# Drive.net
KiCad netlist of a schematic drawn in Altium Designer
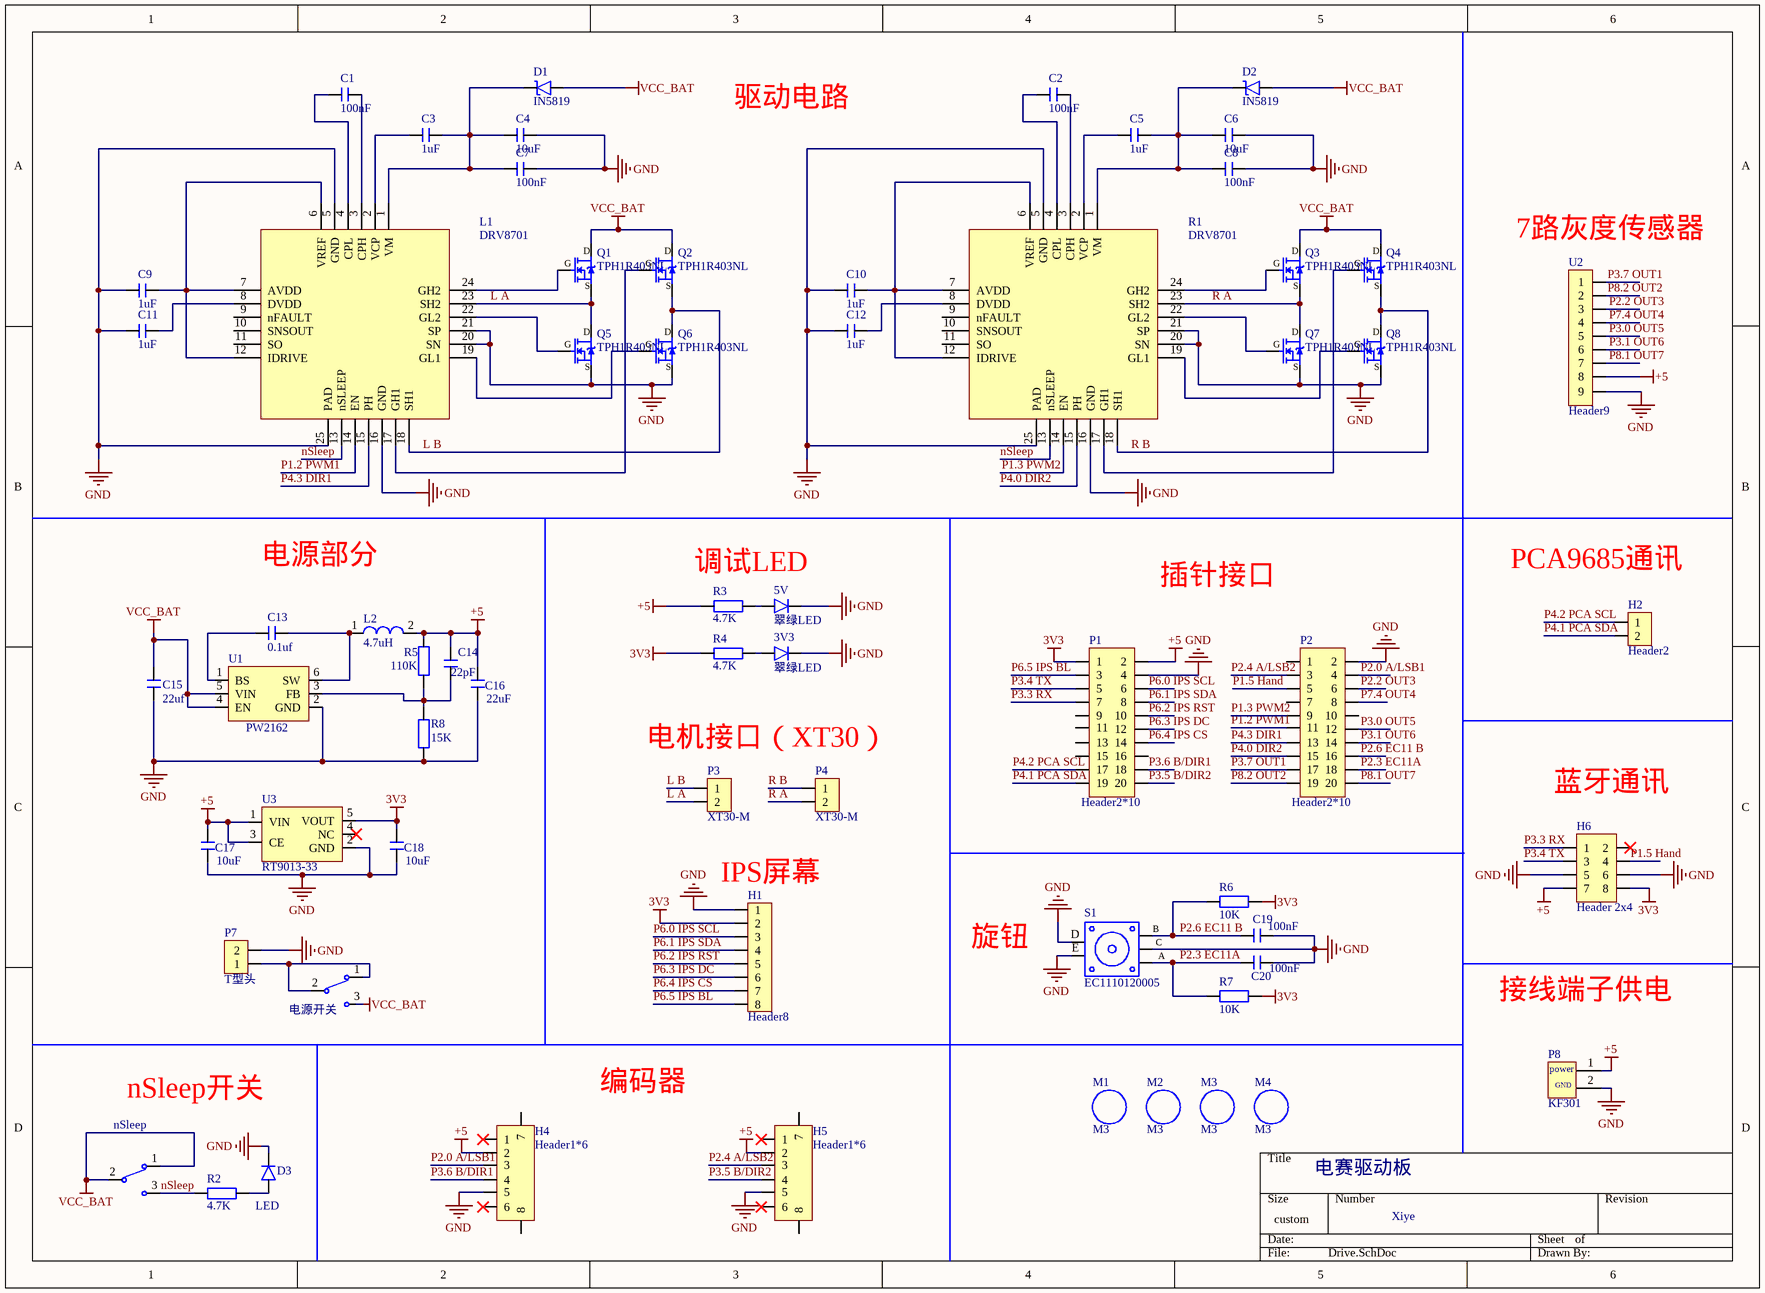
[diagram p0: Drive.SchDoc]

(export (version "E")
  (design (tool "Eeschema 10.0.6"))
  (components
    (comp (ref "3V3") (value "翠绿LED") (footprint "翠绿LED") (libsource (lib "Schlib1") (part "翠绿LED")))
    (comp (ref "5V") (value "翠绿LED") (footprint "翠绿LED") (libsource (lib "Schlib1") (part "翠绿LED")))
    (comp (ref "C1") (value "100nF") (footprint "0603") (libsource (lib "原理图库") (part "电容")))
    (comp (ref "C2") (value "100nF") (footprint "0603") (libsource (lib "原理图库") (part "电容")))
    (comp (ref "C3") (value "1uF") (footprint "0603") (libsource (lib "原理图库") (part "电容")))
    (comp (ref "C4") (value "10uF") (footprint "0603") (libsource (lib "原理图库") (part "电容")))
    (comp (ref "C5") (value "1uF") (footprint "0603") (libsource (lib "原理图库") (part "电容")))
    (comp (ref "C6") (value "10uF") (footprint "0603") (libsource (lib "原理图库") (part "电容")))
    (comp (ref "C7") (value "100nF") (footprint "0603") (libsource (lib "原理图库") (part "电容")))
    (comp (ref "C8") (value "100nF") (footprint "0603") (libsource (lib "原理图库") (part "电容")))
    (comp (ref "C9") (value "1uF") (footprint "0603") (libsource (lib "原理图库") (part "电容")))
    (comp (ref "C10") (value "1uF") (footprint "0603") (libsource (lib "原理图库") (part "电容")))
    (comp (ref "C11") (value "1uF") (footprint "0603") (libsource (lib "原理图库") (part "电容")))
    (comp (ref "C12") (value "1uF") (footprint "0603") (libsource (lib "原理图库") (part "电容")))
    (comp (ref "C13") (value "0.1uf") (footprint "0603") (libsource (lib "原理图库") (part "电容")))
    (comp (ref "C14") (value "22pF") (footprint "0603") (libsource (lib "原理图库") (part "电容")))
    (comp (ref "C15") (value "22uf") (footprint "0603") (libsource (lib "原理图库") (part "电容")))
    (comp (ref "C16") (value "22uF") (footprint "0603") (libsource (lib "原理图库") (part "电容")))
    (comp (ref "C17") (value "10uF") (footprint "0603") (libsource (lib "原理图库") (part "电容")))
    (comp (ref "C18") (value "10uF") (footprint "0603") (libsource (lib "原理图库") (part "电容")))
    (comp (ref "C19") (value "100nF") (footprint "0603") (libsource (lib "原理图库") (part "电容")))
    (comp (ref "C20") (value "100nF") (footprint "0603") (libsource (lib "原理图库") (part "电容")))
    (comp (ref "D1")
      (value "IN5819")
      (footprint "IN5819")
      (description "肖特基二极管")
      (libsource (lib "原理图库") (part "IN5819"))
    )
    (comp (ref "D2")
      (value "IN5819")
      (footprint "IN5819")
      (description "肖特基二极管")
      (libsource (lib "原理图库") (part "IN5819"))
    )
    (comp (ref "D3") (value "LED") (footprint "翠绿LED") (libsource (lib "原理图库") (part "翠绿LED")))
    (comp (ref "H1")
      (value "Header8")
      (footprint "Header8")
      (description "插针1*8 2.54mm")
      (libsource (lib "原理图库") (part "Header8"))
    )
    (comp (ref "H2") (value "Header2") (footprint "Header2") (libsource (lib "原理图库") (part "Header2")))
    (comp (ref "H4") (value "Header1*6") (footprint "XH 1x6p 直插") (libsource (lib "原理图库") (part "Header1*6")))
    (comp (ref "H5") (value "Header1*6") (footprint "XH 1x6p 直插") (libsource (lib "原理图库") (part "Header1*6")))
    (comp (ref "H6")
      (value "Header 2x4")
      (footprint "Header2x4")
      (libsource (lib "原理图库") (part "Header 2x4"))
    )
    (comp (ref "L1")
      (value "DRV8701")
      (footprint "DRV8701")
      (description "刷式直流电机驱动器")
      (libsource (lib "原理图库") (part "DRV8701"))
    )
    (comp (ref "L2") (value "4.7uH") (footprint "252010") (libsource (lib "原理图库") (part "电感")))
    (comp (ref "M1") (value "M3") (footprint "M3限位孔") (libsource (lib "原理图库") (part "M3")))
    (comp (ref "M2") (value "M3") (footprint "M3限位孔") (libsource (lib "原理图库") (part "M3")))
    (comp (ref "M3") (value "M3") (footprint "M3限位孔") (libsource (lib "原理图库") (part "M3")))
    (comp (ref "M4") (value "M3") (footprint "M3限位孔") (libsource (lib "原理图库") (part "M3")))
    (comp (ref "nSleep")
      (value "nSleep")
      (footprint "扭子开关3脚")
      (description "MT-0-103-A101-M200")
      (libsource (lib "原理图库") (part "扭子开关 三脚"))
    )
    (comp (ref "P1") (value "Header2*10") (footprint "2*10排母") (libsource (lib "原理图库") (part "Header2*10")))
    (comp (ref "P2") (value "Header2*10") (footprint "2*10排母") (libsource (lib "原理图库") (part "Header2*10")))
    (comp (ref "P3")
      (value "XT30-M")
      (footprint "XT30-M - duplicate")
      (libsource (lib "原理图库") (part "XT30-M"))
    )
    (comp (ref "P4")
      (value "XT30-M")
      (footprint "XT30-M - duplicate")
      (libsource (lib "原理图库") (part "XT30-M"))
    )
    (comp (ref "P7") (value "T型头") (footprint "T型头") (libsource (lib "原理图库") (part "T型头")))
    (comp (ref "P8")
      (value "KF301")
      (footprint "KF301-2P")
      (description "接线端子")
      (libsource (lib "原理图库") (part "KF301"))
    )
    (comp (ref "Q1")
      (value "TPH1R403NL")
      (footprint "TPH1R403NL")
      (description "MOS管")
      (libsource (lib "原理图库") (part "TPH1R403NL"))
    )
    (comp (ref "Q2")
      (value "TPH1R403NL")
      (footprint "TPH1R403NL")
      (description "MOS管")
      (libsource (lib "原理图库") (part "TPH1R403NL"))
    )
    (comp (ref "Q3")
      (value "TPH1R403NL")
      (footprint "TPH1R403NL")
      (description "MOS管")
      (libsource (lib "原理图库") (part "TPH1R403NL"))
    )
    (comp (ref "Q4")
      (value "TPH1R403NL")
      (footprint "TPH1R403NL")
      (description "MOS管")
      (libsource (lib "原理图库") (part "TPH1R403NL"))
    )
    (comp (ref "Q5")
      (value "TPH1R403NL")
      (footprint "TPH1R403NL")
      (description "MOS管")
      (libsource (lib "原理图库") (part "TPH1R403NL"))
    )
    (comp (ref "Q6")
      (value "TPH1R403NL")
      (footprint "TPH1R403NL")
      (description "MOS管")
      (libsource (lib "原理图库") (part "TPH1R403NL"))
    )
    (comp (ref "Q7")
      (value "TPH1R403NL")
      (footprint "TPH1R403NL")
      (description "MOS管")
      (libsource (lib "原理图库") (part "TPH1R403NL"))
    )
    (comp (ref "Q8")
      (value "TPH1R403NL")
      (footprint "TPH1R403NL")
      (description "MOS管")
      (libsource (lib "原理图库") (part "TPH1R403NL"))
    )
    (comp (ref "R1")
      (value "DRV8701")
      (footprint "DRV8701")
      (description "刷式直流电机驱动器")
      (libsource (lib "原理图库") (part "DRV8701"))
    )
    (comp (ref "R2") (value "4.7K") (footprint "0603") (libsource (lib "原理图库") (part "电阻")))
    (comp (ref "R3") (value "4.7K") (footprint "0603") (libsource (lib "原理图库") (part "电阻")))
    (comp (ref "R4") (value "4.7K") (footprint "0603") (libsource (lib "原理图库") (part "电阻")))
    (comp (ref "R5") (value "110K") (footprint "0603") (libsource (lib "原理图库") (part "电阻")))
    (comp (ref "R6") (value "10K") (footprint "0603") (libsource (lib "原理图库") (part "电阻")))
    (comp (ref "R7") (value "10K") (footprint "0603") (libsource (lib "原理图库") (part "电阻")))
    (comp (ref "R8") (value "15K") (footprint "0603") (libsource (lib "原理图库") (part "电阻")))
    (comp (ref "S1")
      (value "EC1110120005")
      (footprint "EC1110120005")
      (description "旋钮")
      (libsource (lib "Schlib1") (part "EC1110120005"))
    )
    (comp (ref "U1")
      (value "PW2162")
      (footprint "SOT23-6")
      (description "降压芯片")
      (libsource (lib "原理图库") (part "PW2162"))
    )
    (comp (ref "U2") (value "Header9") (footprint "Header9") (libsource (lib "原理图库") (part "Header9")))
    (comp (ref "U3")
      (value "RT9013-33")
      (footprint "SOP23-5")
      (description "5v转3v3 限流500mA")
      (libsource (lib "原理图库") (part "TPRT9013-33"))
    )
    (comp (ref "电源开关")
      (value "电源输入")
      (footprint "扭子开关3脚")
      (description "MT-0-103-A101-M200")
      (libsource (lib "原理图库") (part "扭子开关 三脚"))
    )
  )
  (nets
    (net (code "1") (name "+5") (class "Default")
      (node (ref "C14") (pin "2") (pintype "passive"))
      (node (ref "C16") (pin "2") (pintype "passive"))
      (node (ref "C17") (pin "2") (pintype "passive"))
      (node (ref "H4") (pin "2") (pinfunction "2_2") (pintype "passive"))
      (node (ref "H5") (pin "2") (pinfunction "2_2") (pintype "passive"))
      (node (ref "H6") (pin "7") (pinfunction "7_7") (pintype "passive"))
      (node (ref "L2") (pin "2") (pinfunction "2_2") (pintype "passive"))
      (node (ref "P1") (pin "2") (pinfunction "2_2") (pintype "passive"))
      (node (ref "P8") (pin "1") (pinfunction "Power_1") (pintype "passive"))
      (node (ref "R3") (pin "2") (pintype "passive"))
      (node (ref "R5") (pin "2") (pintype "passive"))
      (node (ref "U2") (pin "8") (pinfunction "8_8") (pintype "passive"))
      (node (ref "U3") (pin "1") (pinfunction "VIN_1") (pintype "passive"))
      (node (ref "U3") (pin "3") (pinfunction "CE_3") (pintype "passive"))
    )
    (net (code "2") (name "/L A") (class "Default")
      (node (ref "L1") (pin "23") (pinfunction "SH2_23") (pintype "passive"))
      (node (ref "P3") (pin "2") (pinfunction "2_2") (pintype "passive"))
      (node (ref "Q1") (pin "2") (pinfunction "S_2") (pintype "passive"))
      (node (ref "Q5") (pin "3") (pinfunction "D_3") (pintype "passive"))
    )
    (net (code "3") (name "/L B") (class "Default")
      (node (ref "L1") (pin "18") (pinfunction "SH1_18") (pintype "passive"))
      (node (ref "P3") (pin "1") (pinfunction "1_1") (pintype "passive"))
      (node (ref "Q2") (pin "2") (pinfunction "S_2") (pintype "passive"))
      (node (ref "Q6") (pin "3") (pinfunction "D_3") (pintype "passive"))
    )
    (net (code "4") (name "/P1.2 PWM1") (class "Default")
      (node (ref "L1") (pin "14") (pinfunction "EN_14") (pintype "passive"))
      (node (ref "P2") (pin "11") (pinfunction "11_11") (pintype "passive"))
    )
    (net (code "5") (name "/P1.3 PWM2") (class "Default")
      (node (ref "P2") (pin "9") (pinfunction "9_9") (pintype "passive"))
      (node (ref "R1") (pin "14") (pinfunction "EN_14") (pintype "passive"))
    )
    (net (code "6") (name "/P1.5 Hand") (class "Default")
      (node (ref "H6") (pin "4") (pinfunction "4_4") (pintype "passive"))
      (node (ref "P2") (pin "5") (pinfunction "5_5") (pintype "passive"))
    )
    (net (code "7") (name "/P2.0 A{slash}LSB1") (class "Default")
      (node (ref "H4") (pin "3") (pinfunction "3_3") (pintype "passive"))
      (node (ref "P2") (pin "4") (pinfunction "4_4") (pintype "passive"))
    )
    (net (code "8") (name "/P2.2 OUT3") (class "Default")
      (node (ref "P2") (pin "6") (pinfunction "6_6") (pintype "passive"))
      (node (ref "U2") (pin "3") (pinfunction "3_3") (pintype "passive"))
    )
    (net (code "9") (name "/P2.3 EC11A") (class "Default")
      (node (ref "C20") (pin "1") (pintype "passive"))
      (node (ref "P2") (pin "18") (pinfunction "18_18") (pintype "passive"))
      (node (ref "R7") (pin "1") (pintype "passive"))
      (node (ref "S1") (pin "A") (pinfunction "A_A") (pintype "passive"))
    )
    (net (code "10") (name "/P2.4 A{slash}LSB2") (class "Default")
      (node (ref "H5") (pin "3") (pinfunction "3_3") (pintype "passive"))
      (node (ref "P2") (pin "3") (pinfunction "3_3") (pintype "passive"))
    )
    (net (code "11") (name "/P2.6 EC11 B") (class "Default")
      (node (ref "C19") (pin "1") (pintype "passive"))
      (node (ref "P2") (pin "16") (pinfunction "16_16") (pintype "passive"))
      (node (ref "R6") (pin "1") (pintype "passive"))
      (node (ref "S1") (pin "B") (pinfunction "B_B") (pintype "passive"))
    )
    (net (code "12") (name "/P3.0 OUT5") (class "Default")
      (node (ref "P2") (pin "12") (pinfunction "12_12") (pintype "passive"))
      (node (ref "U2") (pin "5") (pinfunction "5_5") (pintype "passive"))
    )
    (net (code "13") (name "/P3.1 OUT6") (class "Default")
      (node (ref "P2") (pin "14") (pinfunction "14_14") (pintype "passive"))
      (node (ref "U2") (pin "6") (pinfunction "6_6") (pintype "passive"))
    )
    (net (code "14") (name "/P3.3 RX") (class "Default")
      (node (ref "H6") (pin "1") (pinfunction "1_1") (pintype "passive"))
      (node (ref "P1") (pin "7") (pinfunction "7_7") (pintype "passive"))
    )
    (net (code "15") (name "/P3.4 TX") (class "Default")
      (node (ref "H6") (pin "3") (pinfunction "3_3") (pintype "passive"))
      (node (ref "P1") (pin "5") (pinfunction "5_5") (pintype "passive"))
    )
    (net (code "16") (name "/P3.5 B{slash}DIR2") (class "Default")
      (node (ref "H5") (pin "4") (pinfunction "4_4") (pintype "passive"))
      (node (ref "P1") (pin "20") (pinfunction "20_20") (pintype "passive"))
    )
    (net (code "17") (name "/P3.6 B{slash}DIR1") (class "Default")
      (node (ref "H4") (pin "4") (pinfunction "4_4") (pintype "passive"))
      (node (ref "P1") (pin "18") (pinfunction "18_18") (pintype "passive"))
    )
    (net (code "18") (name "/P3.7 OUT1") (class "Default")
      (node (ref "P2") (pin "17") (pinfunction "17_17") (pintype "passive"))
      (node (ref "U2") (pin "1") (pinfunction "1_1") (pintype "passive"))
    )
    (net (code "19") (name "/P4.0 DIR2") (class "Default")
      (node (ref "P2") (pin "15") (pinfunction "15_15") (pintype "passive"))
      (node (ref "R1") (pin "15") (pinfunction "PH_15") (pintype "passive"))
    )
    (net (code "20") (name "/P4.1 PCA SDA") (class "Default")
      (node (ref "H2") (pin "2") (pinfunction "2_2") (pintype "passive"))
      (node (ref "P1") (pin "19") (pinfunction "19_19") (pintype "passive"))
    )
    (net (code "21") (name "/P4.2 PCA SCL") (class "Default")
      (node (ref "H2") (pin "1") (pinfunction "1_1") (pintype "passive"))
      (node (ref "P1") (pin "17") (pinfunction "17_17") (pintype "passive"))
    )
    (net (code "22") (name "/P4.3 DIR1") (class "Default")
      (node (ref "L1") (pin "15") (pinfunction "PH_15") (pintype "passive"))
      (node (ref "P2") (pin "13") (pinfunction "13_13") (pintype "passive"))
    )
    (net (code "23") (name "/P6.0 IPS SCL") (class "Default")
      (node (ref "H1") (pin "3") (pinfunction "3_3") (pintype "passive"))
      (node (ref "P1") (pin "6") (pinfunction "6_6") (pintype "passive"))
    )
    (net (code "24") (name "/P6.1 IPS SDA") (class "Default")
      (node (ref "H1") (pin "4") (pinfunction "4_4") (pintype "passive"))
      (node (ref "P1") (pin "8") (pinfunction "8_8") (pintype "passive"))
    )
    (net (code "25") (name "/P6.2 IPS RST") (class "Default")
      (node (ref "H1") (pin "5") (pinfunction "5_5") (pintype "passive"))
      (node (ref "P1") (pin "10") (pinfunction "10_10") (pintype "passive"))
    )
    (net (code "26") (name "/P6.3 IPS DC") (class "Default")
      (node (ref "H1") (pin "6") (pinfunction "6_6") (pintype "passive"))
      (node (ref "P1") (pin "12") (pinfunction "12_12") (pintype "passive"))
    )
    (net (code "27") (name "/P6.4 IPS CS") (class "Default")
      (node (ref "H1") (pin "7") (pinfunction "7_7") (pintype "passive"))
      (node (ref "P1") (pin "14") (pinfunction "14_14") (pintype "passive"))
    )
    (net (code "28") (name "/P6.5 IPS BL") (class "Default")
      (node (ref "H1") (pin "8") (pinfunction "8_8") (pintype "passive"))
      (node (ref "P1") (pin "3") (pinfunction "3_3") (pintype "passive"))
    )
    (net (code "29") (name "/P7.4 OUT4") (class "Default")
      (node (ref "P2") (pin "8") (pinfunction "8_8") (pintype "passive"))
      (node (ref "U2") (pin "4") (pinfunction "4_4") (pintype "passive"))
    )
    (net (code "30") (name "/P8.1 OUT7") (class "Default")
      (node (ref "P2") (pin "20") (pinfunction "20_20") (pintype "passive"))
      (node (ref "U2") (pin "7") (pinfunction "7_7") (pintype "passive"))
    )
    (net (code "31") (name "/P8.2 OUT2") (class "Default")
      (node (ref "P2") (pin "19") (pinfunction "19_19") (pintype "passive"))
      (node (ref "U2") (pin "2") (pinfunction "2_2") (pintype "passive"))
    )
    (net (code "32") (name "/R A") (class "Default")
      (node (ref "P4") (pin "2") (pinfunction "2_2") (pintype "passive"))
      (node (ref "Q3") (pin "2") (pinfunction "S_2") (pintype "passive"))
      (node (ref "Q7") (pin "3") (pinfunction "D_3") (pintype "passive"))
      (node (ref "R1") (pin "23") (pinfunction "SH2_23") (pintype "passive"))
    )
    (net (code "33") (name "/R B") (class "Default")
      (node (ref "P4") (pin "1") (pinfunction "1_1") (pintype "passive"))
      (node (ref "Q4") (pin "2") (pinfunction "S_2") (pintype "passive"))
      (node (ref "Q8") (pin "3") (pinfunction "D_3") (pintype "passive"))
      (node (ref "R1") (pin "18") (pinfunction "SH1_18") (pintype "passive"))
    )
    (net (code "34") (name "/nSleep") (class "Default")
      (node (ref "L1") (pin "13") (pinfunction "nSLEEP_13") (pintype "passive"))
      (node (ref "R1") (pin "13") (pinfunction "nSLEEP_13") (pintype "passive"))
      (node (ref "R2") (pin "1") (pintype "passive"))
      (node (ref "nSleep") (pin "3") (pinfunction "3_3") (pintype "passive"))
    )
    (net (code "35") (name "3V3") (class "Default")
      (node (ref "C18") (pin "2") (pintype "passive"))
      (node (ref "H1") (pin "2") (pinfunction "2_2") (pintype "passive"))
      (node (ref "H6") (pin "8") (pinfunction "8_8") (pintype "passive"))
      (node (ref "P1") (pin "1") (pinfunction "1_1") (pintype "passive"))
      (node (ref "R4") (pin "2") (pintype "passive"))
      (node (ref "R6") (pin "2") (pintype "passive"))
      (node (ref "R7") (pin "2") (pintype "passive"))
      (node (ref "U3") (pin "5") (pinfunction "VOUT_5") (pintype "passive"))
    )
    (net (code "36") (name "GND") (class "Default")
      (node (ref "3V3") (pin "2") (pintype "passive"))
      (node (ref "5V") (pin "2") (pintype "passive"))
      (node (ref "C10") (pin "1") (pintype "passive"))
      (node (ref "C11") (pin "1") (pintype "passive"))
      (node (ref "C12") (pin "1") (pintype "passive"))
      (node (ref "C15") (pin "1") (pintype "passive"))
      (node (ref "C16") (pin "1") (pintype "passive"))
      (node (ref "C17") (pin "1") (pintype "passive"))
      (node (ref "C18") (pin "1") (pintype "passive"))
      (node (ref "C19") (pin "2") (pintype "passive"))
      (node (ref "C20") (pin "2") (pintype "passive"))
      (node (ref "C4") (pin "2") (pintype "passive"))
      (node (ref "C6") (pin "2") (pintype "passive"))
      (node (ref "C7") (pin "2") (pintype "passive"))
      (node (ref "C8") (pin "2") (pintype "passive"))
      (node (ref "C9") (pin "1") (pintype "passive"))
      (node (ref "D3") (pin "2") (pintype "passive"))
      (node (ref "H1") (pin "1") (pinfunction "1_1") (pintype "passive"))
      (node (ref "H4") (pin "5") (pinfunction "5_5") (pintype "passive"))
      (node (ref "H5") (pin "5") (pinfunction "5_5") (pintype "passive"))
      (node (ref "H6") (pin "5") (pinfunction "5_5") (pintype "passive"))
      (node (ref "H6") (pin "6") (pinfunction "6_6") (pintype "passive"))
      (node (ref "L1") (pin "16") (pinfunction "GND_16") (pintype "passive"))
      (node (ref "L1") (pin "20") (pinfunction "SN_20") (pintype "passive"))
      (node (ref "L1") (pin "21") (pinfunction "SP_21") (pintype "passive"))
      (node (ref "L1") (pin "25") (pinfunction "PAD_25") (pintype "passive"))
      (node (ref "L1") (pin "5") (pinfunction "GND_5") (pintype "passive"))
      (node (ref "P1") (pin "4") (pinfunction "4_4") (pintype "passive"))
      (node (ref "P2") (pin "2") (pinfunction "2_2") (pintype "passive"))
      (node (ref "P7") (pin "2") (pinfunction "2_2") (pintype "passive"))
      (node (ref "P8") (pin "2") (pinfunction "9_2") (pintype "passive"))
      (node (ref "Q5") (pin "2") (pinfunction "S_2") (pintype "passive"))
      (node (ref "Q6") (pin "2") (pinfunction "S_2") (pintype "passive"))
      (node (ref "Q7") (pin "2") (pinfunction "S_2") (pintype "passive"))
      (node (ref "Q8") (pin "2") (pinfunction "S_2") (pintype "passive"))
      (node (ref "R1") (pin "16") (pinfunction "GND_16") (pintype "passive"))
      (node (ref "R1") (pin "20") (pinfunction "SN_20") (pintype "passive"))
      (node (ref "R1") (pin "21") (pinfunction "SP_21") (pintype "passive"))
      (node (ref "R1") (pin "25") (pinfunction "PAD_25") (pintype "passive"))
      (node (ref "R1") (pin "5") (pinfunction "GND_5") (pintype "passive"))
      (node (ref "R8") (pin "1") (pintype "passive"))
      (node (ref "S1") (pin "C") (pinfunction "C_C") (pintype "passive"))
      (node (ref "S1") (pin "D") (pinfunction "D_D") (pintype "passive"))
      (node (ref "S1") (pin "E") (pinfunction "E_E") (pintype "passive"))
      (node (ref "U1") (pin "2") (pinfunction "GND_2") (pintype "passive"))
      (node (ref "U2") (pin "9") (pinfunction "9_9") (pintype "passive"))
      (node (ref "U3") (pin "2") (pinfunction "GND_2") (pintype "passive"))
    )
    (net (code "37") (name "Net-(3V3-Pad1)") (class "Default")
      (node (ref "3V3") (pin "1") (pintype "passive"))
      (node (ref "R4") (pin "1") (pintype "passive"))
    )
    (net (code "38") (name "Net-(5V-Pad1)") (class "Default")
      (node (ref "5V") (pin "1") (pintype "passive"))
      (node (ref "R3") (pin "1") (pintype "passive"))
    )
    (net (code "39") (name "Net-(D3-Pad1)") (class "Default")
      (node (ref "D3") (pin "1") (pintype "passive"))
      (node (ref "R2") (pin "2") (pintype "passive"))
    )
    (net (code "40") (name "Net-(L1-AVDD)") (class "Default")
      (node (ref "C9") (pin "2") (pintype "passive"))
      (node (ref "L1") (pin "12") (pinfunction "IDRIVE_12") (pintype "passive"))
      (node (ref "L1") (pin "6") (pinfunction "VREF_6") (pintype "passive"))
      (node (ref "L1") (pin "7") (pinfunction "AVDD_7") (pintype "passive"))
    )
    (net (code "41") (name "Net-(L1-CPH)") (class "Default")
      (node (ref "C1") (pin "2") (pintype "passive"))
      (node (ref "L1") (pin "3") (pinfunction "CPH_3") (pintype "passive"))
    )
    (net (code "42") (name "Net-(L1-CPL)") (class "Default")
      (node (ref "C1") (pin "1") (pintype "passive"))
      (node (ref "L1") (pin "4") (pinfunction "CPL_4") (pintype "passive"))
    )
    (net (code "43") (name "Net-(L1-DVDD)") (class "Default")
      (node (ref "C11") (pin "2") (pintype "passive"))
      (node (ref "L1") (pin "8") (pinfunction "DVDD_8") (pintype "passive"))
    )
    (net (code "44") (name "Net-(L1-GH1)") (class "Default")
      (node (ref "L1") (pin "17") (pinfunction "GH1_17") (pintype "passive"))
      (node (ref "Q2") (pin "1") (pinfunction "G_1") (pintype "passive"))
    )
    (net (code "45") (name "Net-(L1-GH2)") (class "Default")
      (node (ref "L1") (pin "24") (pinfunction "GH2_24") (pintype "passive"))
      (node (ref "Q1") (pin "1") (pinfunction "G_1") (pintype "passive"))
    )
    (net (code "46") (name "Net-(L1-GL1)") (class "Default")
      (node (ref "L1") (pin "19") (pinfunction "GL1_19") (pintype "passive"))
      (node (ref "Q6") (pin "1") (pinfunction "G_1") (pintype "passive"))
    )
    (net (code "47") (name "Net-(L1-GL2)") (class "Default")
      (node (ref "L1") (pin "22") (pinfunction "GL2_22") (pintype "passive"))
      (node (ref "Q5") (pin "1") (pinfunction "G_1") (pintype "passive"))
    )
    (net (code "48") (name "Net-(L1-VCP)") (class "Default")
      (node (ref "C3") (pin "1") (pintype "passive"))
      (node (ref "L1") (pin "2") (pinfunction "VCP_2") (pintype "passive"))
    )
    (net (code "49") (name "Net-(L1-VM)") (class "Default")
      (node (ref "C3") (pin "2") (pintype "passive"))
      (node (ref "C4") (pin "1") (pintype "passive"))
      (node (ref "C7") (pin "1") (pintype "passive"))
      (node (ref "D1") (pin "2") (pintype "passive"))
      (node (ref "L1") (pin "1") (pinfunction "VM_1") (pintype "passive"))
    )
    (net (code "50") (name "Net-(P7-Pad1)") (class "Default")
      (node (ref "P7") (pin "1") (pinfunction "1_1") (pintype "passive"))
      (node (ref "电源开关") (pin "1") (pinfunction "1_1") (pintype "passive"))
      (node (ref "电源开关") (pin "2") (pinfunction "2_2") (pintype "passive"))
    )
    (net (code "51") (name "Net-(Q3-G)") (class "Default")
      (node (ref "Q3") (pin "1") (pinfunction "G_1") (pintype "passive"))
      (node (ref "R1") (pin "24") (pinfunction "GH2_24") (pintype "passive"))
    )
    (net (code "52") (name "Net-(Q4-G)") (class "Default")
      (node (ref "Q4") (pin "1") (pinfunction "G_1") (pintype "passive"))
      (node (ref "R1") (pin "17") (pinfunction "GH1_17") (pintype "passive"))
    )
    (net (code "53") (name "Net-(Q7-G)") (class "Default")
      (node (ref "Q7") (pin "1") (pinfunction "G_1") (pintype "passive"))
      (node (ref "R1") (pin "22") (pinfunction "GL2_22") (pintype "passive"))
    )
    (net (code "54") (name "Net-(Q8-G)") (class "Default")
      (node (ref "Q8") (pin "1") (pinfunction "G_1") (pintype "passive"))
      (node (ref "R1") (pin "19") (pinfunction "GL1_19") (pintype "passive"))
    )
    (net (code "55") (name "Net-(R1-AVDD)") (class "Default")
      (node (ref "C10") (pin "2") (pintype "passive"))
      (node (ref "R1") (pin "12") (pinfunction "IDRIVE_12") (pintype "passive"))
      (node (ref "R1") (pin "6") (pinfunction "VREF_6") (pintype "passive"))
      (node (ref "R1") (pin "7") (pinfunction "AVDD_7") (pintype "passive"))
    )
    (net (code "56") (name "Net-(R1-CPH)") (class "Default")
      (node (ref "C2") (pin "2") (pintype "passive"))
      (node (ref "R1") (pin "3") (pinfunction "CPH_3") (pintype "passive"))
    )
    (net (code "57") (name "Net-(R1-CPL)") (class "Default")
      (node (ref "C2") (pin "1") (pintype "passive"))
      (node (ref "R1") (pin "4") (pinfunction "CPL_4") (pintype "passive"))
    )
    (net (code "58") (name "Net-(R1-DVDD)") (class "Default")
      (node (ref "C12") (pin "2") (pintype "passive"))
      (node (ref "R1") (pin "8") (pinfunction "DVDD_8") (pintype "passive"))
    )
    (net (code "59") (name "Net-(R1-VCP)") (class "Default")
      (node (ref "C5") (pin "1") (pintype "passive"))
      (node (ref "R1") (pin "2") (pinfunction "VCP_2") (pintype "passive"))
    )
    (net (code "60") (name "Net-(R1-VM)") (class "Default")
      (node (ref "C5") (pin "2") (pintype "passive"))
      (node (ref "C6") (pin "1") (pintype "passive"))
      (node (ref "C8") (pin "1") (pintype "passive"))
      (node (ref "D2") (pin "2") (pintype "passive"))
      (node (ref "R1") (pin "1") (pinfunction "VM_1") (pintype "passive"))
    )
    (net (code "61") (name "Net-(U1-BS)") (class "Default")
      (node (ref "C13") (pin "1") (pintype "passive"))
      (node (ref "U1") (pin "1") (pinfunction "BS_1") (pintype "passive"))
    )
    (net (code "62") (name "Net-(U1-FB)") (class "Default")
      (node (ref "C14") (pin "1") (pintype "passive"))
      (node (ref "R5") (pin "1") (pintype "passive"))
      (node (ref "R8") (pin "2") (pintype "passive"))
      (node (ref "U1") (pin "3") (pinfunction "FB_3") (pintype "passive"))
    )
    (net (code "63") (name "Net-(U1-SW)") (class "Default")
      (node (ref "C13") (pin "2") (pintype "passive"))
      (node (ref "L2") (pin "1") (pinfunction "1_1") (pintype "passive"))
      (node (ref "U1") (pin "6") (pinfunction "SW_6") (pintype "passive"))
    )
    (net (code "64") (name "VCC_BAT") (class "Default")
      (node (ref "C15") (pin "2") (pintype "passive"))
      (node (ref "D1") (pin "1") (pintype "passive"))
      (node (ref "D2") (pin "1") (pintype "passive"))
      (node (ref "Q1") (pin "3") (pinfunction "D_3") (pintype "passive"))
      (node (ref "Q2") (pin "3") (pinfunction "D_3") (pintype "passive"))
      (node (ref "Q3") (pin "3") (pinfunction "D_3") (pintype "passive"))
      (node (ref "Q4") (pin "3") (pinfunction "D_3") (pintype "passive"))
      (node (ref "U1") (pin "4") (pinfunction "EN_4") (pintype "passive"))
      (node (ref "U1") (pin "5") (pinfunction "VIN_5") (pintype "passive"))
      (node (ref "nSleep") (pin "1") (pinfunction "1_1") (pintype "passive"))
      (node (ref "nSleep") (pin "2") (pinfunction "2_2") (pintype "passive"))
      (node (ref "电源开关") (pin "3") (pinfunction "3_3") (pintype "passive"))
    )
    (net (code "65") (name "unconnected-(H4-Pad1)") (class "Default")
      (node (ref "H4") (pin "1") (pinfunction "1_1") (pintype "passive+no_connect"))
    )
    (net (code "66") (name "unconnected-(H4-Pad6)") (class "Default")
      (node (ref "H4") (pin "6") (pinfunction "6_6") (pintype "passive+no_connect"))
    )
    (net (code "67") (name "unconnected-(H4-Pad7)") (class "Default")
      (node (ref "H4") (pin "7") (pinfunction "7_7") (pintype "passive"))
    )
    (net (code "68") (name "unconnected-(H4-Pad8)") (class "Default")
      (node (ref "H4") (pin "8") (pinfunction "8_8") (pintype "passive"))
    )
    (net (code "69") (name "unconnected-(H5-Pad1)") (class "Default")
      (node (ref "H5") (pin "1") (pinfunction "1_1") (pintype "passive+no_connect"))
    )
    (net (code "70") (name "unconnected-(H5-Pad6)") (class "Default")
      (node (ref "H5") (pin "6") (pinfunction "6_6") (pintype "passive+no_connect"))
    )
    (net (code "71") (name "unconnected-(H5-Pad7)") (class "Default")
      (node (ref "H5") (pin "7") (pinfunction "7_7") (pintype "passive"))
    )
    (net (code "72") (name "unconnected-(H5-Pad8)") (class "Default")
      (node (ref "H5") (pin "8") (pinfunction "8_8") (pintype "passive"))
    )
    (net (code "73") (name "unconnected-(H6-Pad2)") (class "Default")
      (node (ref "H6") (pin "2") (pinfunction "2_2") (pintype "passive+no_connect"))
    )
    (net (code "74") (name "unconnected-(L1-SNSOUT-Pad10)") (class "Default")
      (node (ref "L1") (pin "10") (pinfunction "SNSOUT_10") (pintype "passive"))
    )
    (net (code "75") (name "unconnected-(L1-SO-Pad11)") (class "Default")
      (node (ref "L1") (pin "11") (pinfunction "SO_11") (pintype "passive"))
    )
    (net (code "76") (name "unconnected-(L1-nFAULT-Pad9)") (class "Default")
      (node (ref "L1") (pin "9") (pinfunction "nFAULT_9") (pintype "passive"))
    )
    (net (code "77") (name "unconnected-(P1-Pad9)") (class "Default")
      (node (ref "P1") (pin "9") (pinfunction "9_9") (pintype "passive"))
    )
    (net (code "78") (name "unconnected-(P1-Pad11)") (class "Default")
      (node (ref "P1") (pin "11") (pinfunction "11_11") (pintype "passive"))
    )
    (net (code "79") (name "unconnected-(P1-Pad13)") (class "Default")
      (node (ref "P1") (pin "13") (pinfunction "13_13") (pintype "passive"))
    )
    (net (code "80") (name "unconnected-(P1-Pad15)") (class "Default")
      (node (ref "P1") (pin "15") (pinfunction "15_15") (pintype "passive"))
    )
    (net (code "81") (name "unconnected-(P1-Pad16)") (class "Default")
      (node (ref "P1") (pin "16") (pinfunction "16_16") (pintype "passive"))
    )
    (net (code "82") (name "unconnected-(P2-Pad1)") (class "Default")
      (node (ref "P2") (pin "1") (pinfunction "1_1") (pintype "passive"))
    )
    (net (code "83") (name "unconnected-(P2-Pad7)") (class "Default")
      (node (ref "P2") (pin "7") (pinfunction "7_7") (pintype "passive"))
    )
    (net (code "84") (name "unconnected-(P2-Pad10)") (class "Default")
      (node (ref "P2") (pin "10") (pinfunction "10_10") (pintype "passive"))
    )
    (net (code "85") (name "unconnected-(R1-SNSOUT-Pad10)") (class "Default")
      (node (ref "R1") (pin "10") (pinfunction "SNSOUT_10") (pintype "passive"))
    )
    (net (code "86") (name "unconnected-(R1-SO-Pad11)") (class "Default")
      (node (ref "R1") (pin "11") (pinfunction "SO_11") (pintype "passive"))
    )
    (net (code "87") (name "unconnected-(R1-nFAULT-Pad9)") (class "Default")
      (node (ref "R1") (pin "9") (pinfunction "nFAULT_9") (pintype "passive"))
    )
    (net (code "88") (name "unconnected-(U3-NC-Pad4)") (class "Default")
      (node (ref "U3") (pin "4") (pinfunction "NC_4") (pintype "passive+no_connect"))
    )
  )
)
